# SCH_terminal_controller_2024-05-08.net
KiCad netlist of a schematic drawn in Altium Designer
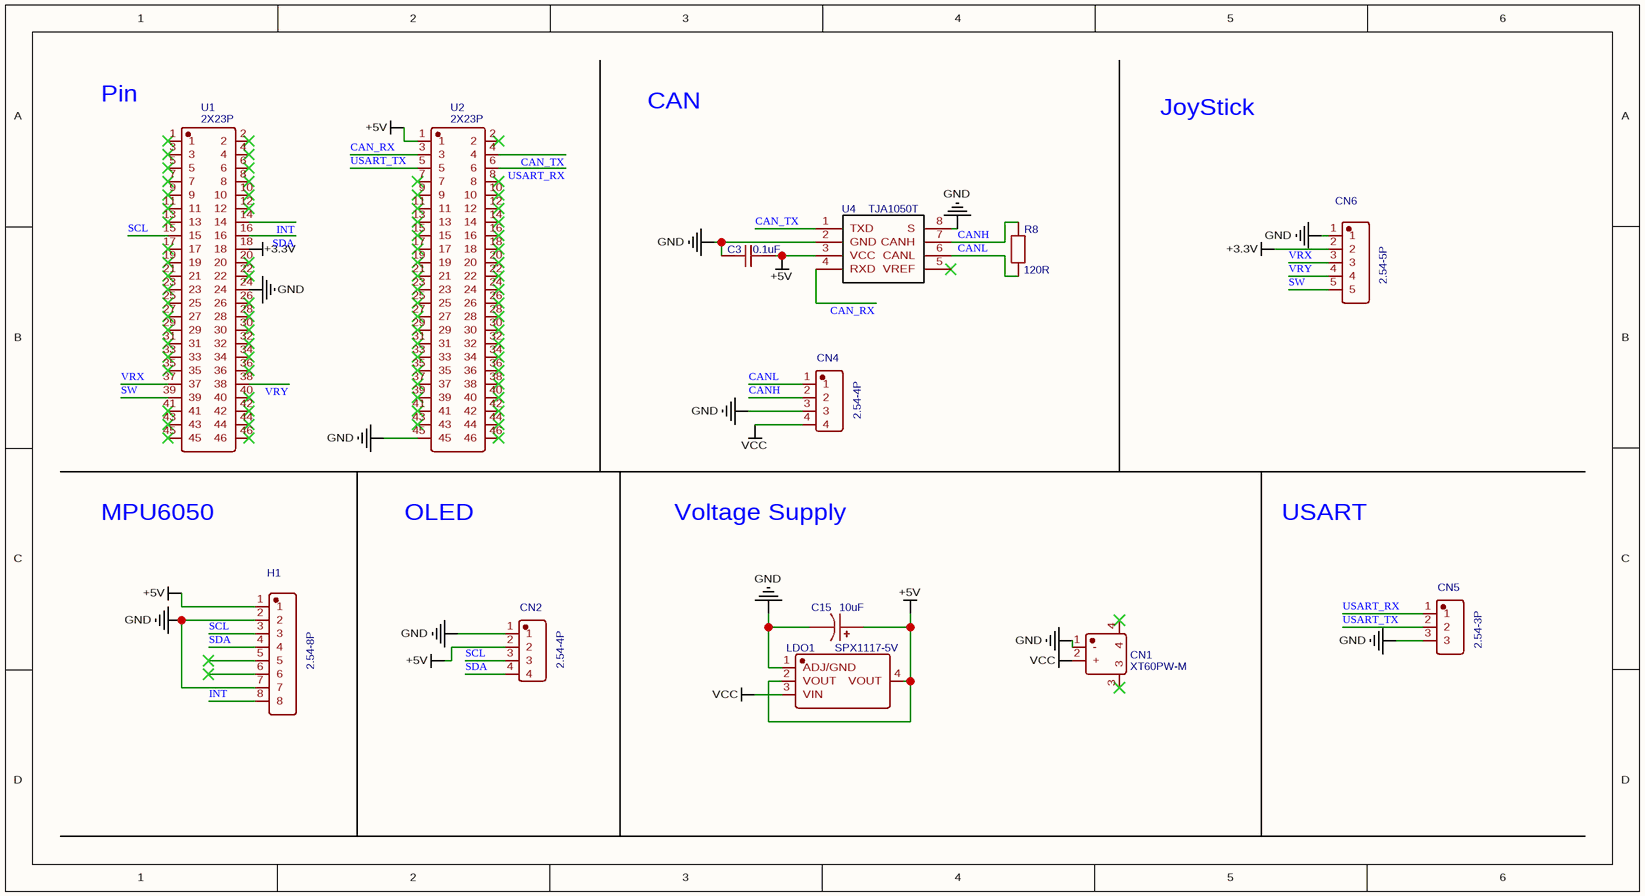
[diagram p0: SCH_terminal_controller_2024-05-08.schdoc]

(export (version "E")
  (design (tool "Eeschema 10.0.6"))
  (components
    (comp (ref "C3")
      (value "0.1uF")
      (fields (field (name "CONTRIBUTOR") "LCEDA_Lib"))
      (libsource (lib "altium-import") (part "root_0_0.1uF_"))
    )
    (comp (ref "C15")
      (value "10uF")
      (fields (field (name "CONTRIBUTOR") "LCEDA_Lib"))
      (libsource (lib "altium-import") (part "root_2_10uF_"))
    )
    (comp (ref "CN1")
      (value "XT60PW-M")
      (fields (field (name "MANUFACTURER") "AMASS(艾迈斯)") (field (name "CONTRIBUTOR") "LCSC"))
      (libsource (lib "altium-import") (part "root_0_XT60PW-M_"))
    )
    (comp (ref "CN2")
      (value "2.54-4P")
      (fields
        (field (name "MANUFACTURER") "HCTL(华灿天禄)")
        (field (name "MANUFACTURER PART") "XH-4AW")
        (field (name "CONTRIBUTOR") "LCSC")
      )
      (libsource (lib "altium-import") (part "root_0_2.54-4P_"))
    )
    (comp (ref "CN4")
      (value "2.54-4P")
      (fields
        (field (name "MANUFACTURER") "HCTL(华灿天禄)")
        (field (name "MANUFACTURER PART") "XH-4AW")
        (field (name "CONTRIBUTOR") "LCSC")
      )
      (libsource (lib "altium-import") (part "root_0_2.54-4P_"))
    )
    (comp (ref "CN5")
      (value "2.54-3P")
      (fields
        (field (name "MANUFACTURER") "HCTL(华灿天禄)")
        (field (name "MANUFACTURER PART") "XH-3AW")
        (field (name "CONTRIBUTOR") "LCSC")
      )
      (libsource (lib "altium-import") (part "root_0_2.54-3P_"))
    )
    (comp (ref "CN6")
      (value "2.54-5P")
      (fields
        (field (name "MANUFACTURER") "HCTL(华灿天禄)")
        (field (name "MANUFACTURER PART") "XH-5AW")
        (field (name "CONTRIBUTOR") "LCSC")
      )
      (libsource (lib "altium-import") (part "root_0_2.54-5P_"))
    )
    (comp (ref "H1")
      (value "2.54-8P")
      (fields
        (field (name "MANUFACTURER") "HCTL(华灿天禄)")
        (field (name "MANUFACTURER PART") "PZ254-1-08-Z-8.5")
        (field (name "CONTRIBUTOR") "LCSC")
      )
      (libsource (lib "altium-import") (part "root_0_2.54-8P_"))
    )
    (comp (ref "LDO1")
      (value "SPX1117-5V")
      (fields
        (field (name "BOM_MANUFACTURER PART") "SPX1117M3-L/TR")
        (field (name "BOM_SUPPLIER PART") "C67402")
      )
      (libsource (lib "altium-import") (part "root_0_SPX1117-5V_"))
    )
    (comp (ref "R8")
      (value "120R")
      (fields (field (name "CONTRIBUTOR") "LCEDA_Lib"))
      (libsource (lib "altium-import") (part "root_1_120R_"))
    )
    (comp (ref "U1")
      (value "2X23P")
      (fields
        (field (name "MANUFACTURER") "XKB Connection(中国星坤)")
        (field (name "MANUFACTURER PART") "X6522WV-2x23H-C60D30-E80")
        (field (name "CONTRIBUTOR") "lcsc")
      )
      (libsource (lib "altium-import") (part "root_0_2X23P_"))
    )
    (comp (ref "U2")
      (value "2X23P")
      (fields
        (field (name "MANUFACTURER") "XKB Connection(中国星坤)")
        (field (name "MANUFACTURER PART") "X6522WV-2x23H-C60D30-E80")
        (field (name "CONTRIBUTOR") "lcsc")
      )
      (libsource (lib "altium-import") (part "root_0_2X23P_"))
    )
    (comp (ref "U4")
      (value "TJA1050T")
      (fields
        (field (name "BOM_MANUFACTURER PART") "TJA1050T/CM,118")
        (field (name "BOM_SUPPLIER PART") "C6952")
      )
      (libsource (lib "altium-import") (part "root_0_TJA1050T_"))
    )
  )
  (nets
    (net (code "1") (name "+3.3V") (class "Default")
      (node (ref "CN6") (pin "2") (pinfunction "2_2") (pintype "passive"))
      (node (ref "U1") (pin "18") (pinfunction "18_18") (pintype "passive"))
    )
    (net (code "2") (name "+5V") (class "Default")
      (node (ref "C15") (pin "1") (pinfunction "1_1") (pintype "passive"))
      (node (ref "C3") (pin "2") (pinfunction "2_2") (pintype "passive"))
      (node (ref "CN2") (pin "2") (pinfunction "2_2") (pintype "passive"))
      (node (ref "H1") (pin "1") (pinfunction "1_1") (pintype "passive"))
      (node (ref "LDO1") (pin "2") (pinfunction "VOUT_2") (pintype "passive"))
      (node (ref "LDO1") (pin "4") (pinfunction "VOUT_4") (pintype "passive"))
      (node (ref "U2") (pin "1") (pinfunction "1_1") (pintype "passive"))
      (node (ref "U4") (pin "3") (pinfunction "VCC_3") (pintype "passive"))
    )
    (net (code "3") (name "/CANH") (class "Default")
      (node (ref "CN4") (pin "2") (pinfunction "2_2") (pintype "passive"))
      (node (ref "R8") (pin "2") (pinfunction "2_2") (pintype "passive"))
      (node (ref "U4") (pin "7") (pinfunction "CANH_7") (pintype "passive"))
    )
    (net (code "4") (name "/CANL") (class "Default")
      (node (ref "CN4") (pin "1") (pinfunction "1_1") (pintype "passive"))
      (node (ref "R8") (pin "1") (pinfunction "1_1") (pintype "passive"))
      (node (ref "U4") (pin "6") (pinfunction "CANL_6") (pintype "passive"))
    )
    (net (code "5") (name "/CAN_RX") (class "Default")
      (node (ref "U2") (pin "3") (pinfunction "3_3") (pintype "passive"))
      (node (ref "U4") (pin "4") (pinfunction "RXD_4") (pintype "passive"))
    )
    (net (code "6") (name "/CAN_TX") (class "Default")
      (node (ref "U2") (pin "4") (pinfunction "4_4") (pintype "passive"))
      (node (ref "U4") (pin "1") (pinfunction "TXD_1") (pintype "passive"))
    )
    (net (code "7") (name "/INT") (class "Default")
      (node (ref "H1") (pin "8") (pinfunction "8_8") (pintype "passive"))
      (node (ref "U1") (pin "14") (pinfunction "14_14") (pintype "passive"))
    )
    (net (code "8") (name "/SCL") (class "Default")
      (node (ref "CN2") (pin "3") (pinfunction "3_3") (pintype "passive"))
      (node (ref "H1") (pin "3") (pinfunction "3_3") (pintype "passive"))
      (node (ref "U1") (pin "15") (pinfunction "15_15") (pintype "passive"))
    )
    (net (code "9") (name "/SDA") (class "Default")
      (node (ref "CN2") (pin "4") (pinfunction "4_4") (pintype "passive"))
      (node (ref "H1") (pin "4") (pinfunction "4_4") (pintype "passive"))
      (node (ref "U1") (pin "16") (pinfunction "16_16") (pintype "passive"))
    )
    (net (code "10") (name "/SW") (class "Default")
      (node (ref "CN6") (pin "5") (pinfunction "5_5") (pintype "passive"))
      (node (ref "U1") (pin "39") (pinfunction "39_39") (pintype "passive"))
    )
    (net (code "11") (name "/USART_RX") (class "Default")
      (node (ref "CN5") (pin "1") (pinfunction "1_1") (pintype "passive"))
      (node (ref "U2") (pin "6") (pinfunction "6_6") (pintype "passive"))
    )
    (net (code "12") (name "/USART_TX") (class "Default")
      (node (ref "CN5") (pin "2") (pinfunction "2_2") (pintype "passive"))
      (node (ref "U2") (pin "5") (pinfunction "5_5") (pintype "passive"))
    )
    (net (code "13") (name "/VRX") (class "Default")
      (node (ref "CN6") (pin "3") (pinfunction "3_3") (pintype "passive"))
      (node (ref "U1") (pin "37") (pinfunction "37_37") (pintype "passive"))
    )
    (net (code "14") (name "/VRY") (class "Default")
      (node (ref "CN6") (pin "4") (pinfunction "4_4") (pintype "passive"))
      (node (ref "U1") (pin "38") (pinfunction "38_38") (pintype "passive"))
    )
    (net (code "15") (name "GND") (class "Default")
      (node (ref "C15") (pin "2") (pinfunction "2_2") (pintype "passive"))
      (node (ref "C3") (pin "1") (pinfunction "1_1") (pintype "passive"))
      (node (ref "CN1") (pin "1") (pinfunction "-_1") (pintype "passive"))
      (node (ref "CN2") (pin "1") (pinfunction "1_1") (pintype "passive"))
      (node (ref "CN4") (pin "3") (pinfunction "3_3") (pintype "passive"))
      (node (ref "CN5") (pin "3") (pinfunction "3_3") (pintype "passive"))
      (node (ref "CN6") (pin "1") (pinfunction "1_1") (pintype "passive"))
      (node (ref "H1") (pin "2") (pinfunction "2_2") (pintype "passive"))
      (node (ref "H1") (pin "7") (pinfunction "7_7") (pintype "passive"))
      (node (ref "LDO1") (pin "1") (pinfunction "ADJ/GND_1") (pintype "passive"))
      (node (ref "U1") (pin "24") (pinfunction "24_24") (pintype "passive"))
      (node (ref "U2") (pin "45") (pinfunction "45_45") (pintype "passive"))
      (node (ref "U4") (pin "2") (pinfunction "GND_2") (pintype "passive"))
      (node (ref "U4") (pin "8") (pinfunction "S_8") (pintype "passive"))
    )
    (net (code "16") (name "VCC") (class "Default")
      (node (ref "CN1") (pin "2") (pinfunction "+_2") (pintype "passive"))
      (node (ref "CN4") (pin "4") (pinfunction "4_4") (pintype "passive"))
      (node (ref "LDO1") (pin "3") (pinfunction "VIN_3") (pintype "passive"))
    )
    (net (code "17") (name "unconnected-(CN1-Pad3)") (class "Default")
      (node (ref "CN1") (pin "3") (pinfunction "3_3") (pintype "passive+no_connect"))
    )
    (net (code "18") (name "unconnected-(CN1-Pad4)") (class "Default")
      (node (ref "CN1") (pin "4") (pinfunction "4_4") (pintype "passive+no_connect"))
    )
    (net (code "19") (name "unconnected-(H1-Pad5)") (class "Default")
      (node (ref "H1") (pin "5") (pinfunction "5_5") (pintype "passive+no_connect"))
    )
    (net (code "20") (name "unconnected-(H1-Pad6)") (class "Default")
      (node (ref "H1") (pin "6") (pinfunction "6_6") (pintype "passive+no_connect"))
    )
    (net (code "21") (name "unconnected-(U1-Pad1)") (class "Default")
      (node (ref "U1") (pin "1") (pinfunction "1_1") (pintype "passive+no_connect"))
    )
    (net (code "22") (name "unconnected-(U1-Pad2)") (class "Default")
      (node (ref "U1") (pin "2") (pinfunction "2_2") (pintype "passive+no_connect"))
    )
    (net (code "23") (name "unconnected-(U1-Pad3)") (class "Default")
      (node (ref "U1") (pin "3") (pinfunction "3_3") (pintype "passive+no_connect"))
    )
    (net (code "24") (name "unconnected-(U1-Pad4)") (class "Default")
      (node (ref "U1") (pin "4") (pinfunction "4_4") (pintype "passive+no_connect"))
    )
    (net (code "25") (name "unconnected-(U1-Pad5)") (class "Default")
      (node (ref "U1") (pin "5") (pinfunction "5_5") (pintype "passive+no_connect"))
    )
    (net (code "26") (name "unconnected-(U1-Pad6)") (class "Default")
      (node (ref "U1") (pin "6") (pinfunction "6_6") (pintype "passive+no_connect"))
    )
    (net (code "27") (name "unconnected-(U1-Pad7)") (class "Default")
      (node (ref "U1") (pin "7") (pinfunction "7_7") (pintype "passive+no_connect"))
    )
    (net (code "28") (name "unconnected-(U1-Pad8)") (class "Default")
      (node (ref "U1") (pin "8") (pinfunction "8_8") (pintype "passive+no_connect"))
    )
    (net (code "29") (name "unconnected-(U1-Pad9)") (class "Default")
      (node (ref "U1") (pin "9") (pinfunction "9_9") (pintype "passive+no_connect"))
    )
    (net (code "30") (name "unconnected-(U1-Pad10)") (class "Default")
      (node (ref "U1") (pin "10") (pinfunction "10_10") (pintype "passive+no_connect"))
    )
    (net (code "31") (name "unconnected-(U1-Pad11)") (class "Default")
      (node (ref "U1") (pin "11") (pinfunction "11_11") (pintype "passive+no_connect"))
    )
    (net (code "32") (name "unconnected-(U1-Pad12)") (class "Default")
      (node (ref "U1") (pin "12") (pinfunction "12_12") (pintype "passive+no_connect"))
    )
    (net (code "33") (name "unconnected-(U1-Pad13)") (class "Default")
      (node (ref "U1") (pin "13") (pinfunction "13_13") (pintype "passive+no_connect"))
    )
    (net (code "34") (name "unconnected-(U1-Pad17)") (class "Default")
      (node (ref "U1") (pin "17") (pinfunction "17_17") (pintype "passive+no_connect"))
    )
    (net (code "35") (name "unconnected-(U1-Pad19)") (class "Default")
      (node (ref "U1") (pin "19") (pinfunction "19_19") (pintype "passive+no_connect"))
    )
    (net (code "36") (name "unconnected-(U1-Pad20)") (class "Default")
      (node (ref "U1") (pin "20") (pinfunction "20_20") (pintype "passive+no_connect"))
    )
    (net (code "37") (name "unconnected-(U1-Pad21)") (class "Default")
      (node (ref "U1") (pin "21") (pinfunction "21_21") (pintype "passive+no_connect"))
    )
    (net (code "38") (name "unconnected-(U1-Pad22)") (class "Default")
      (node (ref "U1") (pin "22") (pinfunction "22_22") (pintype "passive+no_connect"))
    )
    (net (code "39") (name "unconnected-(U1-Pad23)") (class "Default")
      (node (ref "U1") (pin "23") (pinfunction "23_23") (pintype "passive+no_connect"))
    )
    (net (code "40") (name "unconnected-(U1-Pad25)") (class "Default")
      (node (ref "U1") (pin "25") (pinfunction "25_25") (pintype "passive+no_connect"))
    )
    (net (code "41") (name "unconnected-(U1-Pad26)") (class "Default")
      (node (ref "U1") (pin "26") (pinfunction "26_26") (pintype "passive+no_connect"))
    )
    (net (code "42") (name "unconnected-(U1-Pad27)") (class "Default")
      (node (ref "U1") (pin "27") (pinfunction "27_27") (pintype "passive+no_connect"))
    )
    (net (code "43") (name "unconnected-(U1-Pad28)") (class "Default")
      (node (ref "U1") (pin "28") (pinfunction "28_28") (pintype "passive+no_connect"))
    )
    (net (code "44") (name "unconnected-(U1-Pad29)") (class "Default")
      (node (ref "U1") (pin "29") (pinfunction "29_29") (pintype "passive+no_connect"))
    )
    (net (code "45") (name "unconnected-(U1-Pad30)") (class "Default")
      (node (ref "U1") (pin "30") (pinfunction "30_30") (pintype "passive+no_connect"))
    )
    (net (code "46") (name "unconnected-(U1-Pad31)") (class "Default")
      (node (ref "U1") (pin "31") (pinfunction "31_31") (pintype "passive+no_connect"))
    )
    (net (code "47") (name "unconnected-(U1-Pad32)") (class "Default")
      (node (ref "U1") (pin "32") (pinfunction "32_32") (pintype "passive+no_connect"))
    )
    (net (code "48") (name "unconnected-(U1-Pad33)") (class "Default")
      (node (ref "U1") (pin "33") (pinfunction "33_33") (pintype "passive+no_connect"))
    )
    (net (code "49") (name "unconnected-(U1-Pad34)") (class "Default")
      (node (ref "U1") (pin "34") (pinfunction "34_34") (pintype "passive+no_connect"))
    )
    (net (code "50") (name "unconnected-(U1-Pad35)") (class "Default")
      (node (ref "U1") (pin "35") (pinfunction "35_35") (pintype "passive+no_connect"))
    )
    (net (code "51") (name "unconnected-(U1-Pad36)") (class "Default")
      (node (ref "U1") (pin "36") (pinfunction "36_36") (pintype "passive+no_connect"))
    )
    (net (code "52") (name "unconnected-(U1-Pad40)") (class "Default")
      (node (ref "U1") (pin "40") (pinfunction "40_40") (pintype "passive+no_connect"))
    )
    (net (code "53") (name "unconnected-(U1-Pad41)") (class "Default")
      (node (ref "U1") (pin "41") (pinfunction "41_41") (pintype "passive+no_connect"))
    )
    (net (code "54") (name "unconnected-(U1-Pad42)") (class "Default")
      (node (ref "U1") (pin "42") (pinfunction "42_42") (pintype "passive+no_connect"))
    )
    (net (code "55") (name "unconnected-(U1-Pad43)") (class "Default")
      (node (ref "U1") (pin "43") (pinfunction "43_43") (pintype "passive+no_connect"))
    )
    (net (code "56") (name "unconnected-(U1-Pad44)") (class "Default")
      (node (ref "U1") (pin "44") (pinfunction "44_44") (pintype "passive+no_connect"))
    )
    (net (code "57") (name "unconnected-(U1-Pad45)") (class "Default")
      (node (ref "U1") (pin "45") (pinfunction "45_45") (pintype "passive+no_connect"))
    )
    (net (code "58") (name "unconnected-(U1-Pad46)") (class "Default")
      (node (ref "U1") (pin "46") (pinfunction "46_46") (pintype "passive+no_connect"))
    )
    (net (code "59") (name "unconnected-(U2-Pad2)") (class "Default")
      (node (ref "U2") (pin "2") (pinfunction "2_2") (pintype "passive+no_connect"))
    )
    (net (code "60") (name "unconnected-(U2-Pad7)") (class "Default")
      (node (ref "U2") (pin "7") (pinfunction "7_7") (pintype "passive+no_connect"))
    )
    (net (code "61") (name "unconnected-(U2-Pad8)") (class "Default")
      (node (ref "U2") (pin "8") (pinfunction "8_8") (pintype "passive+no_connect"))
    )
    (net (code "62") (name "unconnected-(U2-Pad9)") (class "Default")
      (node (ref "U2") (pin "9") (pinfunction "9_9") (pintype "passive+no_connect"))
    )
    (net (code "63") (name "unconnected-(U2-Pad10)") (class "Default")
      (node (ref "U2") (pin "10") (pinfunction "10_10") (pintype "passive+no_connect"))
    )
    (net (code "64") (name "unconnected-(U2-Pad11)") (class "Default")
      (node (ref "U2") (pin "11") (pinfunction "11_11") (pintype "passive+no_connect"))
    )
    (net (code "65") (name "unconnected-(U2-Pad12)") (class "Default")
      (node (ref "U2") (pin "12") (pinfunction "12_12") (pintype "passive+no_connect"))
    )
    (net (code "66") (name "unconnected-(U2-Pad13)") (class "Default")
      (node (ref "U2") (pin "13") (pinfunction "13_13") (pintype "passive+no_connect"))
    )
    (net (code "67") (name "unconnected-(U2-Pad14)") (class "Default")
      (node (ref "U2") (pin "14") (pinfunction "14_14") (pintype "passive+no_connect"))
    )
    (net (code "68") (name "unconnected-(U2-Pad15)") (class "Default")
      (node (ref "U2") (pin "15") (pinfunction "15_15") (pintype "passive+no_connect"))
    )
    (net (code "69") (name "unconnected-(U2-Pad16)") (class "Default")
      (node (ref "U2") (pin "16") (pinfunction "16_16") (pintype "passive+no_connect"))
    )
    (net (code "70") (name "unconnected-(U2-Pad17)") (class "Default")
      (node (ref "U2") (pin "17") (pinfunction "17_17") (pintype "passive+no_connect"))
    )
    (net (code "71") (name "unconnected-(U2-Pad18)") (class "Default")
      (node (ref "U2") (pin "18") (pinfunction "18_18") (pintype "passive+no_connect"))
    )
    (net (code "72") (name "unconnected-(U2-Pad19)") (class "Default")
      (node (ref "U2") (pin "19") (pinfunction "19_19") (pintype "passive+no_connect"))
    )
    (net (code "73") (name "unconnected-(U2-Pad20)") (class "Default")
      (node (ref "U2") (pin "20") (pinfunction "20_20") (pintype "passive+no_connect"))
    )
    (net (code "74") (name "unconnected-(U2-Pad21)") (class "Default")
      (node (ref "U2") (pin "21") (pinfunction "21_21") (pintype "passive+no_connect"))
    )
    (net (code "75") (name "unconnected-(U2-Pad22)") (class "Default")
      (node (ref "U2") (pin "22") (pinfunction "22_22") (pintype "passive+no_connect"))
    )
    (net (code "76") (name "unconnected-(U2-Pad23)") (class "Default")
      (node (ref "U2") (pin "23") (pinfunction "23_23") (pintype "passive+no_connect"))
    )
    (net (code "77") (name "unconnected-(U2-Pad24)") (class "Default")
      (node (ref "U2") (pin "24") (pinfunction "24_24") (pintype "passive+no_connect"))
    )
    (net (code "78") (name "unconnected-(U2-Pad25)") (class "Default")
      (node (ref "U2") (pin "25") (pinfunction "25_25") (pintype "passive+no_connect"))
    )
    (net (code "79") (name "unconnected-(U2-Pad26)") (class "Default")
      (node (ref "U2") (pin "26") (pinfunction "26_26") (pintype "passive+no_connect"))
    )
    (net (code "80") (name "unconnected-(U2-Pad27)") (class "Default")
      (node (ref "U2") (pin "27") (pinfunction "27_27") (pintype "passive+no_connect"))
    )
    (net (code "81") (name "unconnected-(U2-Pad28)") (class "Default")
      (node (ref "U2") (pin "28") (pinfunction "28_28") (pintype "passive+no_connect"))
    )
    (net (code "82") (name "unconnected-(U2-Pad29)") (class "Default")
      (node (ref "U2") (pin "29") (pinfunction "29_29") (pintype "passive+no_connect"))
    )
    (net (code "83") (name "unconnected-(U2-Pad30)") (class "Default")
      (node (ref "U2") (pin "30") (pinfunction "30_30") (pintype "passive+no_connect"))
    )
    (net (code "84") (name "unconnected-(U2-Pad31)") (class "Default")
      (node (ref "U2") (pin "31") (pinfunction "31_31") (pintype "passive+no_connect"))
    )
    (net (code "85") (name "unconnected-(U2-Pad32)") (class "Default")
      (node (ref "U2") (pin "32") (pinfunction "32_32") (pintype "passive+no_connect"))
    )
    (net (code "86") (name "unconnected-(U2-Pad33)") (class "Default")
      (node (ref "U2") (pin "33") (pinfunction "33_33") (pintype "passive+no_connect"))
    )
    (net (code "87") (name "unconnected-(U2-Pad34)") (class "Default")
      (node (ref "U2") (pin "34") (pinfunction "34_34") (pintype "passive+no_connect"))
    )
    (net (code "88") (name "unconnected-(U2-Pad35)") (class "Default")
      (node (ref "U2") (pin "35") (pinfunction "35_35") (pintype "passive+no_connect"))
    )
    (net (code "89") (name "unconnected-(U2-Pad36)") (class "Default")
      (node (ref "U2") (pin "36") (pinfunction "36_36") (pintype "passive+no_connect"))
    )
    (net (code "90") (name "unconnected-(U2-Pad37)") (class "Default")
      (node (ref "U2") (pin "37") (pinfunction "37_37") (pintype "passive+no_connect"))
    )
    (net (code "91") (name "unconnected-(U2-Pad38)") (class "Default")
      (node (ref "U2") (pin "38") (pinfunction "38_38") (pintype "passive+no_connect"))
    )
    (net (code "92") (name "unconnected-(U2-Pad39)") (class "Default")
      (node (ref "U2") (pin "39") (pinfunction "39_39") (pintype "passive+no_connect"))
    )
    (net (code "93") (name "unconnected-(U2-Pad40)") (class "Default")
      (node (ref "U2") (pin "40") (pinfunction "40_40") (pintype "passive+no_connect"))
    )
    (net (code "94") (name "unconnected-(U2-Pad41)") (class "Default")
      (node (ref "U2") (pin "41") (pinfunction "41_41") (pintype "passive+no_connect"))
    )
    (net (code "95") (name "unconnected-(U2-Pad42)") (class "Default")
      (node (ref "U2") (pin "42") (pinfunction "42_42") (pintype "passive+no_connect"))
    )
    (net (code "96") (name "unconnected-(U2-Pad43)") (class "Default")
      (node (ref "U2") (pin "43") (pinfunction "43_43") (pintype "passive+no_connect"))
    )
    (net (code "97") (name "unconnected-(U2-Pad44)") (class "Default")
      (node (ref "U2") (pin "44") (pinfunction "44_44") (pintype "passive+no_connect"))
    )
    (net (code "98") (name "unconnected-(U2-Pad46)") (class "Default")
      (node (ref "U2") (pin "46") (pinfunction "46_46") (pintype "passive+no_connect"))
    )
    (net (code "99") (name "unconnected-(U4-VREF-Pad5)") (class "Default")
      (node (ref "U4") (pin "5") (pinfunction "VREF_5") (pintype "passive+no_connect"))
    )
  )
)
